# SoC_GTR.net
KiCad netlist of a schematic drawn in Altium Designer
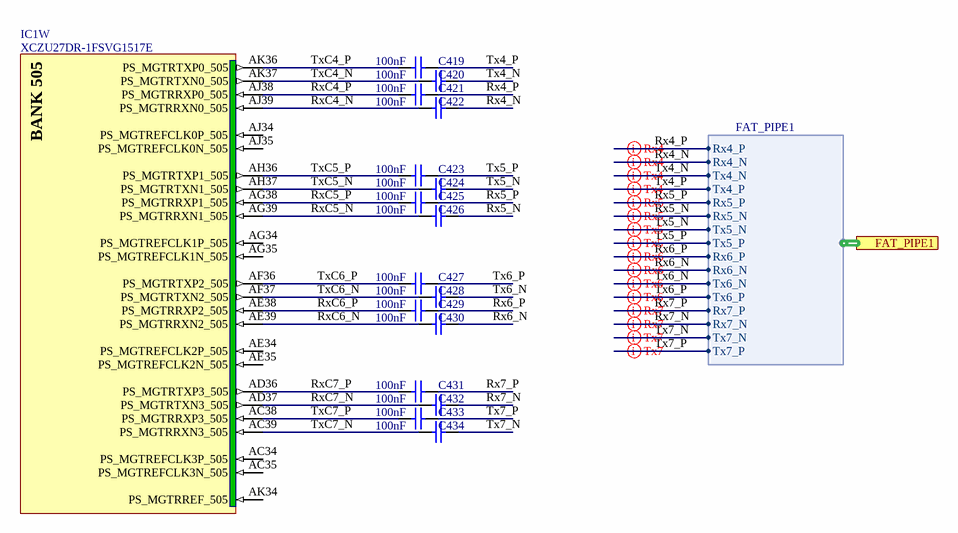
[diagram p0: SoC_GTR.SchDoc]

(export (version "E")
  (design (tool "Eeschema 10.0.6"))
  (components
    (comp (ref "C419")
      (value "100nF")
      (footprint "CAPC0603X33N")
      (description "Non-polarised capacitor")
      (fields
        (field (name "PART NUMBER") "CC0201_100NF_6.3V_10%_X5R")
        (field (name "VOLTAGE") "6.3V")
        (field (name "AUTHOR") "CERN DEM JLC")
      )
      (libsource (lib "Capacitors") (part "Capacitor - non polarized"))
    )
    (comp (ref "C420")
      (value "100nF")
      (footprint "CAPC0603X33N")
      (description "Non-polarised capacitor")
      (fields
        (field (name "PART NUMBER") "CC0201_100NF_6.3V_10%_X5R")
        (field (name "VOLTAGE") "6.3V")
        (field (name "AUTHOR") "CERN DEM JLC")
      )
      (libsource (lib "Capacitors") (part "Capacitor - non polarized"))
    )
    (comp (ref "C421")
      (value "100nF")
      (footprint "CAPC0603X33N")
      (description "Non-polarised capacitor")
      (fields
        (field (name "PART NUMBER") "CC0201_100NF_6.3V_10%_X5R")
        (field (name "VOLTAGE") "6.3V")
        (field (name "AUTHOR") "CERN DEM JLC")
      )
      (libsource (lib "Capacitors") (part "Capacitor - non polarized"))
    )
    (comp (ref "C422")
      (value "100nF")
      (footprint "CAPC0603X33N")
      (description "Non-polarised capacitor")
      (fields
        (field (name "PART NUMBER") "CC0201_100NF_6.3V_10%_X5R")
        (field (name "VOLTAGE") "6.3V")
        (field (name "AUTHOR") "CERN DEM JLC")
      )
      (libsource (lib "Capacitors") (part "Capacitor - non polarized"))
    )
    (comp (ref "C423")
      (value "100nF")
      (footprint "CAPC0603X33N")
      (description "Non-polarised capacitor")
      (fields
        (field (name "PART NUMBER") "CC0201_100NF_6.3V_10%_X5R")
        (field (name "VOLTAGE") "6.3V")
        (field (name "AUTHOR") "CERN DEM JLC")
      )
      (libsource (lib "Capacitors") (part "Capacitor - non polarized"))
    )
    (comp (ref "C424")
      (value "100nF")
      (footprint "CAPC0603X33N")
      (description "Non-polarised capacitor")
      (fields
        (field (name "PART NUMBER") "CC0201_100NF_6.3V_10%_X5R")
        (field (name "VOLTAGE") "6.3V")
        (field (name "AUTHOR") "CERN DEM JLC")
      )
      (libsource (lib "Capacitors") (part "Capacitor - non polarized"))
    )
    (comp (ref "C425")
      (value "100nF")
      (footprint "CAPC0603X33N")
      (description "Non-polarised capacitor")
      (fields
        (field (name "PART NUMBER") "CC0201_100NF_6.3V_10%_X5R")
        (field (name "VOLTAGE") "6.3V")
        (field (name "AUTHOR") "CERN DEM JLC")
      )
      (libsource (lib "Capacitors") (part "Capacitor - non polarized"))
    )
    (comp (ref "C426")
      (value "100nF")
      (footprint "CAPC0603X33N")
      (description "Non-polarised capacitor")
      (fields
        (field (name "PART NUMBER") "CC0201_100NF_6.3V_10%_X5R")
        (field (name "VOLTAGE") "6.3V")
        (field (name "AUTHOR") "CERN DEM JLC")
      )
      (libsource (lib "Capacitors") (part "Capacitor - non polarized"))
    )
    (comp (ref "C427")
      (value "100nF")
      (footprint "CAPC0603X33N")
      (description "Non-polarised capacitor")
      (fields
        (field (name "PART NUMBER") "CC0201_100NF_6.3V_10%_X5R")
        (field (name "VOLTAGE") "6.3V")
        (field (name "AUTHOR") "CERN DEM JLC")
      )
      (libsource (lib "Capacitors") (part "Capacitor - non polarized"))
    )
    (comp (ref "C428")
      (value "100nF")
      (footprint "CAPC0603X33N")
      (description "Non-polarised capacitor")
      (fields
        (field (name "PART NUMBER") "CC0201_100NF_6.3V_10%_X5R")
        (field (name "VOLTAGE") "6.3V")
        (field (name "AUTHOR") "CERN DEM JLC")
      )
      (libsource (lib "Capacitors") (part "Capacitor - non polarized"))
    )
    (comp (ref "C429")
      (value "100nF")
      (footprint "CAPC0603X33N")
      (description "Non-polarised capacitor")
      (fields
        (field (name "PART NUMBER") "CC0201_100NF_6.3V_10%_X5R")
        (field (name "VOLTAGE") "6.3V")
        (field (name "AUTHOR") "CERN DEM JLC")
      )
      (libsource (lib "Capacitors") (part "Capacitor - non polarized"))
    )
    (comp (ref "C430")
      (value "100nF")
      (footprint "CAPC0603X33N")
      (description "Non-polarised capacitor")
      (fields
        (field (name "PART NUMBER") "CC0201_100NF_6.3V_10%_X5R")
        (field (name "VOLTAGE") "6.3V")
        (field (name "AUTHOR") "CERN DEM JLC")
      )
      (libsource (lib "Capacitors") (part "Capacitor - non polarized"))
    )
    (comp (ref "C431")
      (value "100nF")
      (footprint "CAPC0603X33N")
      (description "Non-polarised capacitor")
      (fields
        (field (name "PART NUMBER") "CC0201_100NF_6.3V_10%_X5R")
        (field (name "VOLTAGE") "6.3V")
        (field (name "AUTHOR") "CERN DEM JLC")
      )
      (libsource (lib "Capacitors") (part "Capacitor - non polarized"))
    )
    (comp (ref "C432")
      (value "100nF")
      (footprint "CAPC0603X33N")
      (description "Non-polarised capacitor")
      (fields
        (field (name "PART NUMBER") "CC0201_100NF_6.3V_10%_X5R")
        (field (name "VOLTAGE") "6.3V")
        (field (name "AUTHOR") "CERN DEM JLC")
      )
      (libsource (lib "Capacitors") (part "Capacitor - non polarized"))
    )
    (comp (ref "C433")
      (value "100nF")
      (footprint "CAPC0603X33N")
      (description "Non-polarised capacitor")
      (fields
        (field (name "PART NUMBER") "CC0201_100NF_6.3V_10%_X5R")
        (field (name "VOLTAGE") "6.3V")
        (field (name "AUTHOR") "CERN DEM JLC")
      )
      (libsource (lib "Capacitors") (part "Capacitor - non polarized"))
    )
    (comp (ref "C434")
      (value "100nF")
      (footprint "CAPC0603X33N")
      (description "Non-polarised capacitor")
      (fields
        (field (name "PART NUMBER") "CC0201_100NF_6.3V_10%_X5R")
        (field (name "VOLTAGE") "6.3V")
        (field (name "AUTHOR") "CERN DEM JLC")
      )
      (libsource (lib "Capacitors") (part "Capacitor - non polarized"))
    )
    (comp (ref "IC1")
      (value "XCZU27DR-1FSVG1517E")
      (footprint "XILINX_FSVG1517 (XCZU27DR)")
      (fields (field (name "MANUFACTURER") "XILINX") (field (name "AUTHOR") "CERN DEM MR"))
      (libsource (lib "ICs And Semiconductors") (part "XCZU27DR-1FSVG1517E"))
    )
  )
  (nets
    (net (code "2") (name "/Rx4_N") (class "Default")
      (node (ref "C422") (pin "2") (pinfunction "2_2") (pintype "passive"))
    )
    (net (code "3") (name "/Rx4_P") (class "Default")
      (node (ref "C421") (pin "2") (pinfunction "2_2") (pintype "passive"))
    )
    (net (code "4") (name "/Rx5_N") (class "Default")
      (node (ref "C426") (pin "2") (pinfunction "2_2") (pintype "passive"))
    )
    (net (code "5") (name "/Rx5_P") (class "Default")
      (node (ref "C425") (pin "2") (pinfunction "2_2") (pintype "passive"))
    )
    (net (code "6") (name "/Rx6_N") (class "Default")
      (node (ref "C430") (pin "2") (pinfunction "2_2") (pintype "passive"))
    )
    (net (code "7") (name "/Rx6_P") (class "Default")
      (node (ref "C429") (pin "2") (pinfunction "2_2") (pintype "passive"))
    )
    (net (code "8") (name "/Rx7_N") (class "Default")
      (node (ref "C432") (pin "2") (pinfunction "2_2") (pintype "passive"))
    )
    (net (code "9") (name "/Rx7_P") (class "Default")
      (node (ref "C431") (pin "2") (pinfunction "2_2") (pintype "passive"))
    )
    (net (code "10") (name "/RxC4_N") (class "Default")
      (node (ref "C422") (pin "1") (pinfunction "1_1") (pintype "passive"))
      (node (ref "IC1") (pin "AJ39") (pinfunction "PS_MGTRRXN0_505_AJ39") (pintype "input"))
    )
    (net (code "11") (name "/RxC4_P") (class "Default")
      (node (ref "C421") (pin "1") (pinfunction "1_1") (pintype "passive"))
      (node (ref "IC1") (pin "AJ38") (pinfunction "PS_MGTRRXP0_505_AJ38") (pintype "input"))
    )
    (net (code "12") (name "/RxC5_N") (class "Default")
      (node (ref "C426") (pin "1") (pinfunction "1_1") (pintype "passive"))
      (node (ref "IC1") (pin "AG39") (pinfunction "PS_MGTRRXN1_505_AG39") (pintype "input"))
    )
    (net (code "13") (name "/RxC5_P") (class "Default")
      (node (ref "C425") (pin "1") (pinfunction "1_1") (pintype "passive"))
      (node (ref "IC1") (pin "AG38") (pinfunction "PS_MGTRRXP1_505_AG38") (pintype "input"))
    )
    (net (code "14") (name "/RxC6_N") (class "Default")
      (node (ref "C430") (pin "1") (pinfunction "1_1") (pintype "passive"))
      (node (ref "IC1") (pin "AE39") (pinfunction "PS_MGTRRXN2_505_AE39") (pintype "input"))
    )
    (net (code "15") (name "/RxC6_P") (class "Default")
      (node (ref "C429") (pin "1") (pinfunction "1_1") (pintype "passive"))
      (node (ref "IC1") (pin "AE38") (pinfunction "PS_MGTRRXP2_505_AE38") (pintype "input"))
    )
    (net (code "16") (name "/RxC7_N") (class "Default")
      (node (ref "C432") (pin "1") (pinfunction "1_1") (pintype "passive"))
      (node (ref "IC1") (pin "AD37") (pinfunction "PS_MGTRTXN3_505_AD37") (pintype "output"))
    )
    (net (code "17") (name "/RxC7_P") (class "Default")
      (node (ref "C431") (pin "1") (pinfunction "1_1") (pintype "passive"))
      (node (ref "IC1") (pin "AD36") (pinfunction "PS_MGTRTXP3_505_AD36") (pintype "output"))
    )
    (net (code "18") (name "/Tx4_N") (class "Default")
      (node (ref "C420") (pin "2") (pinfunction "2_2") (pintype "passive"))
    )
    (net (code "19") (name "/Tx4_P") (class "Default")
      (node (ref "C419") (pin "2") (pinfunction "2_2") (pintype "passive"))
    )
    (net (code "20") (name "/Tx5_N") (class "Default")
      (node (ref "C424") (pin "2") (pinfunction "2_2") (pintype "passive"))
    )
    (net (code "21") (name "/Tx5_P") (class "Default")
      (node (ref "C423") (pin "2") (pinfunction "2_2") (pintype "passive"))
    )
    (net (code "22") (name "/Tx6_N") (class "Default")
      (node (ref "C428") (pin "2") (pinfunction "2_2") (pintype "passive"))
    )
    (net (code "23") (name "/Tx6_P") (class "Default")
      (node (ref "C427") (pin "2") (pinfunction "2_2") (pintype "passive"))
    )
    (net (code "24") (name "/Tx7_N") (class "Default")
      (node (ref "C434") (pin "2") (pinfunction "2_2") (pintype "passive"))
    )
    (net (code "25") (name "/Tx7_P") (class "Default")
      (node (ref "C433") (pin "2") (pinfunction "2_2") (pintype "passive"))
    )
    (net (code "26") (name "/TxC4_N") (class "Default")
      (node (ref "C420") (pin "1") (pinfunction "1_1") (pintype "passive"))
      (node (ref "IC1") (pin "AK37") (pinfunction "PS_MGTRTXN0_505_AK37") (pintype "output"))
    )
    (net (code "27") (name "/TxC4_P") (class "Default")
      (node (ref "C419") (pin "1") (pinfunction "1_1") (pintype "passive"))
      (node (ref "IC1") (pin "AK36") (pinfunction "PS_MGTRTXP0_505_AK36") (pintype "output"))
    )
    (net (code "28") (name "/TxC5_N") (class "Default")
      (node (ref "C424") (pin "1") (pinfunction "1_1") (pintype "passive"))
      (node (ref "IC1") (pin "AH37") (pinfunction "PS_MGTRTXN1_505_AH37") (pintype "output"))
    )
    (net (code "29") (name "/TxC5_P") (class "Default")
      (node (ref "C423") (pin "1") (pinfunction "1_1") (pintype "passive"))
      (node (ref "IC1") (pin "AH36") (pinfunction "PS_MGTRTXP1_505_AH36") (pintype "output"))
    )
    (net (code "30") (name "/TxC6_N") (class "Default")
      (node (ref "C428") (pin "1") (pinfunction "1_1") (pintype "passive"))
      (node (ref "IC1") (pin "AF37") (pinfunction "PS_MGTRTXN2_505_AF37") (pintype "output"))
    )
    (net (code "31") (name "/TxC6_P") (class "Default")
      (node (ref "C427") (pin "1") (pinfunction "1_1") (pintype "passive"))
      (node (ref "IC1") (pin "AF36") (pinfunction "PS_MGTRTXP2_505_AF36") (pintype "output"))
    )
    (net (code "32") (name "/TxC7_N") (class "Default")
      (node (ref "C434") (pin "1") (pinfunction "1_1") (pintype "passive"))
      (node (ref "IC1") (pin "AC39") (pinfunction "PS_MGTRRXN3_505_AC39") (pintype "input"))
    )
    (net (code "33") (name "/TxC7_P") (class "Default")
      (node (ref "C433") (pin "1") (pinfunction "1_1") (pintype "passive"))
      (node (ref "IC1") (pin "AC38") (pinfunction "PS_MGTRRXP3_505_AC38") (pintype "input"))
    )
    (net (code "35") (name "unconnected-(IC1W-PS_MGTREFCLK0N_505-PadAJ35)") (class "Default")
      (node (ref "IC1") (pin "AJ35") (pinfunction "PS_MGTREFCLK0N_505_AJ35") (pintype "input"))
    )
    (net (code "36") (name "unconnected-(IC1W-PS_MGTREFCLK0P_505-PadAJ34)") (class "Default")
      (node (ref "IC1") (pin "AJ34") (pinfunction "PS_MGTREFCLK0P_505_AJ34") (pintype "input"))
    )
    (net (code "37") (name "unconnected-(IC1W-PS_MGTREFCLK1N_505-PadAG35)") (class "Default")
      (node (ref "IC1") (pin "AG35") (pinfunction "PS_MGTREFCLK1N_505_AG35") (pintype "input"))
    )
    (net (code "38") (name "unconnected-(IC1W-PS_MGTREFCLK1P_505-PadAG34)") (class "Default")
      (node (ref "IC1") (pin "AG34") (pinfunction "PS_MGTREFCLK1P_505_AG34") (pintype "input"))
    )
    (net (code "39") (name "unconnected-(IC1W-PS_MGTREFCLK2N_505-PadAE35)") (class "Default")
      (node (ref "IC1") (pin "AE35") (pinfunction "PS_MGTREFCLK2N_505_AE35") (pintype "input"))
    )
    (net (code "40") (name "unconnected-(IC1W-PS_MGTREFCLK2P_505-PadAE34)") (class "Default")
      (node (ref "IC1") (pin "AE34") (pinfunction "PS_MGTREFCLK2P_505_AE34") (pintype "input"))
    )
    (net (code "41") (name "unconnected-(IC1W-PS_MGTREFCLK3N_505-PadAC35)") (class "Default")
      (node (ref "IC1") (pin "AC35") (pinfunction "PS_MGTREFCLK3N_505_AC35") (pintype "input"))
    )
    (net (code "42") (name "unconnected-(IC1W-PS_MGTREFCLK3P_505-PadAC34)") (class "Default")
      (node (ref "IC1") (pin "AC34") (pinfunction "PS_MGTREFCLK3P_505_AC34") (pintype "input"))
    )
    (net (code "43") (name "unconnected-(IC1W-PS_MGTRREF_505-PadAK34)") (class "Default")
      (node (ref "IC1") (pin "AK34") (pinfunction "PS_MGTRREF_505_AK34") (pintype "input"))
    )
  )
)
